# cw312_template_microcontroller.net
KiCad netlist of a schematic drawn in Altium Designer
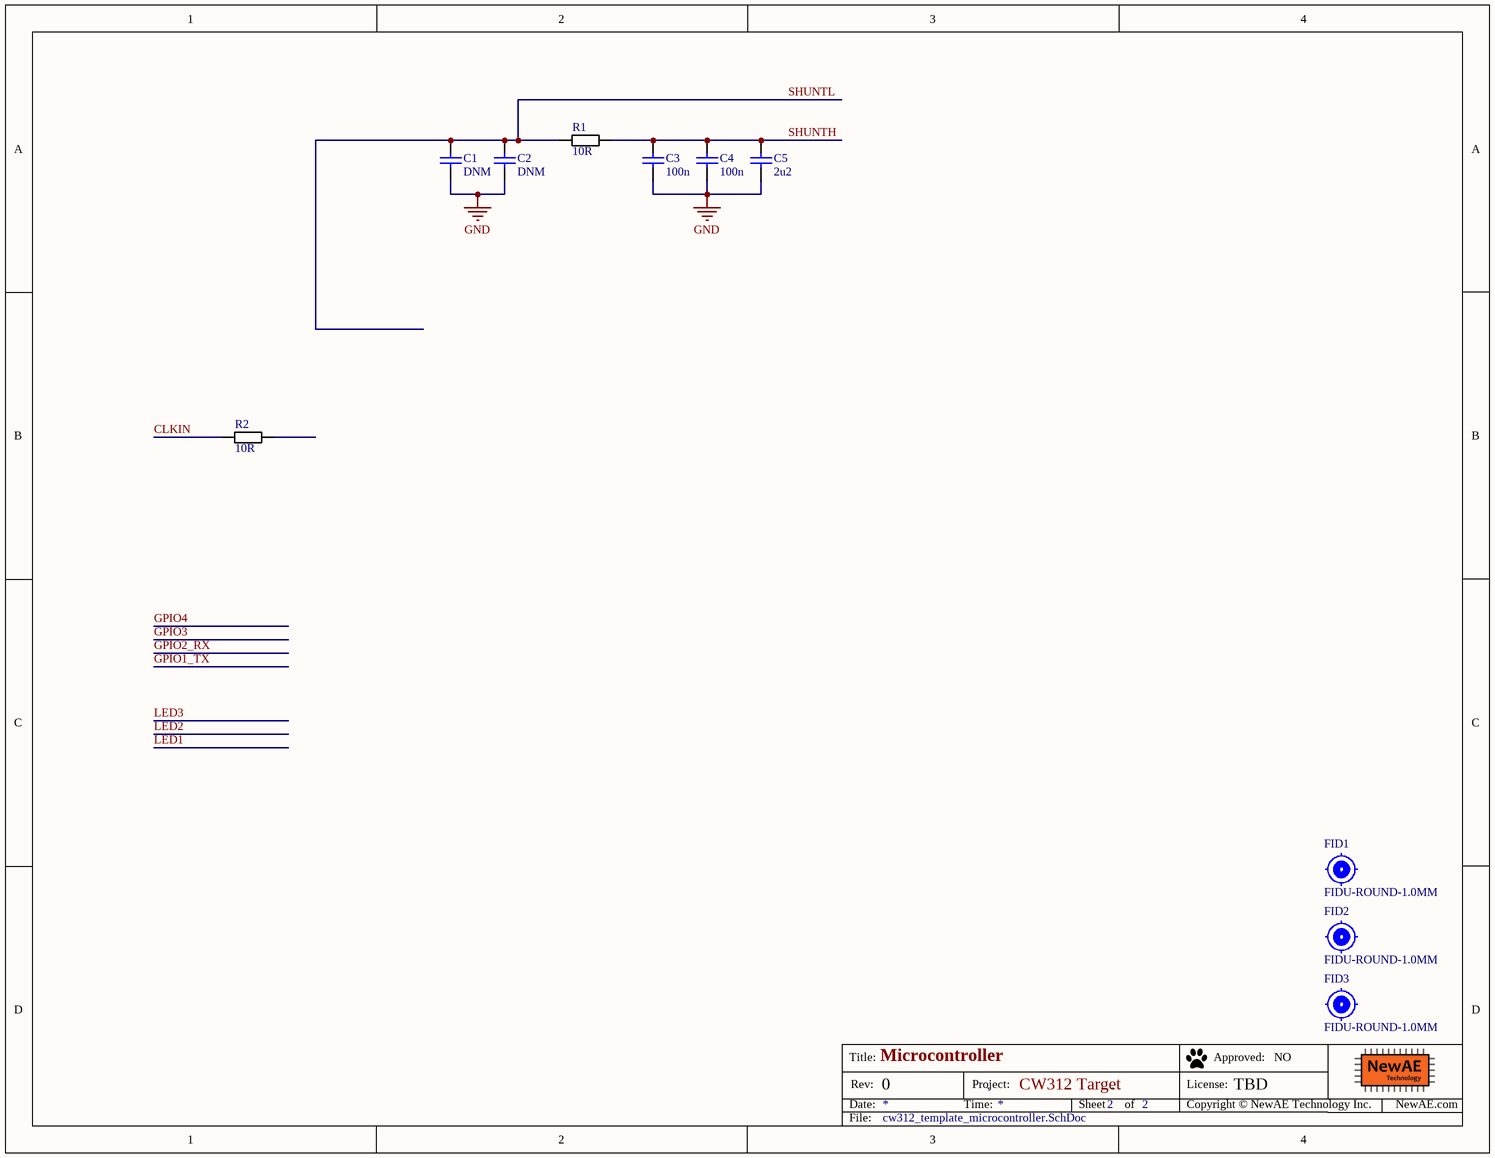
[diagram p0: cw312_template_microcontroller.SchDoc]

(export (version "E")
  (design (tool "Eeschema 10.0.6"))
  (components
    (comp (ref "C1")
      (value "DNM")
      (footprint "CAPC0603_M")
      (fields (field (name "PART NUMBER") "CCHIP-100n-0603"))
      (libsource (lib "NewAE_AltiumLib") (part "CAP"))
    )
    (comp (ref "C2")
      (value "DNM")
      (footprint "CAPC0603_M")
      (fields (field (name "PART NUMBER") "CCHIP-100n-0603"))
      (libsource (lib "NewAE_AltiumLib") (part "CAP"))
    )
    (comp (ref "C3")
      (value "100n")
      (footprint "CAPC0603_M")
      (description "100n, 0603")
      (fields (field (name "PART NUMBER") "CCHIP-100n-0603"))
      (libsource (lib "NewAE_AltiumLib") (part "CAP"))
    )
    (comp (ref "C4")
      (value "100n")
      (footprint "CAPC0603_M")
      (description "100n, 0603")
      (fields (field (name "PART NUMBER") "CCHIP-100n-0603"))
      (libsource (lib "NewAE_AltiumLib") (part "CAP"))
    )
    (comp (ref "C5")
      (value "2u2")
      (footprint "CAPC0603_M")
      (description "2u2, 0603")
      (fields (field (name "PART NUMBER") "CCHIP-2u2-0603"))
      (libsource (lib "NewAE_AltiumLib") (part "CAP"))
    )
    (comp (ref "FID1")
      (value "FIDU-ROUND-1.0MM")
      (footprint "FIDU-ROUND-1.0mm")
      (description "ROUND FIDUCIAL")
      (libsource (lib "NewAE_AltiumLib") (part "FIDU-ROUND-1.0MM"))
    )
    (comp (ref "FID2")
      (value "FIDU-ROUND-1.0MM")
      (footprint "FIDU-ROUND-1.0mm")
      (description "ROUND FIDUCIAL")
      (libsource (lib "NewAE_AltiumLib") (part "FIDU-ROUND-1.0MM"))
    )
    (comp (ref "FID3")
      (value "FIDU-ROUND-1.0MM")
      (footprint "FIDU-ROUND-1.0mm")
      (description "ROUND FIDUCIAL")
      (libsource (lib "NewAE_AltiumLib") (part "FIDU-ROUND-1.0MM"))
    )
    (comp (ref "R1")
      (value "10R")
      (footprint "RESC1608X55N")
      (description "10R res, 0603, 1%, 1/10W")
      (fields (field (name "PART NUMBER") "RCHIP-10R-0603") (field (name "TOLERANCE") "1%"))
      (libsource (lib "NewAE_AltiumLib") (part "RES-EU"))
    )
    (comp (ref "R2")
      (value "10R")
      (footprint "RESC1608X55N")
      (description "10R res, 0603, 1%, 1/10W")
      (fields (field (name "PART NUMBER") "RCHIP-10R-0603") (field (name "TOLERANCE") "1%"))
      (libsource (lib "NewAE_AltiumLib") (part "RES-EU"))
    )
  )
  (nets
    (net (code "1") (name "/CLKIN") (class "Default")
      (node (ref "R2") (pin "1") (pinfunction "1_1") (pintype "passive"))
    )
    (net (code "9") (name "/SHUNTH") (class "Default")
      (node (ref "C3") (pin "1") (pinfunction "1_1") (pintype "passive"))
      (node (ref "C4") (pin "1") (pinfunction "1_1") (pintype "passive"))
      (node (ref "C5") (pin "1") (pinfunction "1_1") (pintype "passive"))
      (node (ref "R1") (pin "2") (pinfunction "2_2") (pintype "passive"))
    )
    (net (code "10") (name "/SHUNTL") (class "Default")
      (node (ref "C1") (pin "1") (pinfunction "1_1") (pintype "passive"))
      (node (ref "C2") (pin "1") (pinfunction "1_1") (pintype "passive"))
      (node (ref "R1") (pin "1") (pinfunction "1_1") (pintype "passive"))
    )
    (net (code "11") (name "GND") (class "Default")
      (node (ref "C1") (pin "2") (pinfunction "2_2") (pintype "passive"))
      (node (ref "C2") (pin "2") (pinfunction "2_2") (pintype "passive"))
      (node (ref "C3") (pin "2") (pinfunction "2_2") (pintype "passive"))
      (node (ref "C4") (pin "2") (pinfunction "2_2") (pintype "passive"))
      (node (ref "C5") (pin "2") (pinfunction "2_2") (pintype "passive"))
    )
    (net (code "12") (name "unconnected-(R2-Pad2)") (class "Default")
      (node (ref "R2") (pin "2") (pinfunction "2_2") (pintype "passive"))
    )
  )
)
